# Nintendo_3DS_USB-C.net
KiCad netlist of a schematic drawn in EAGLE
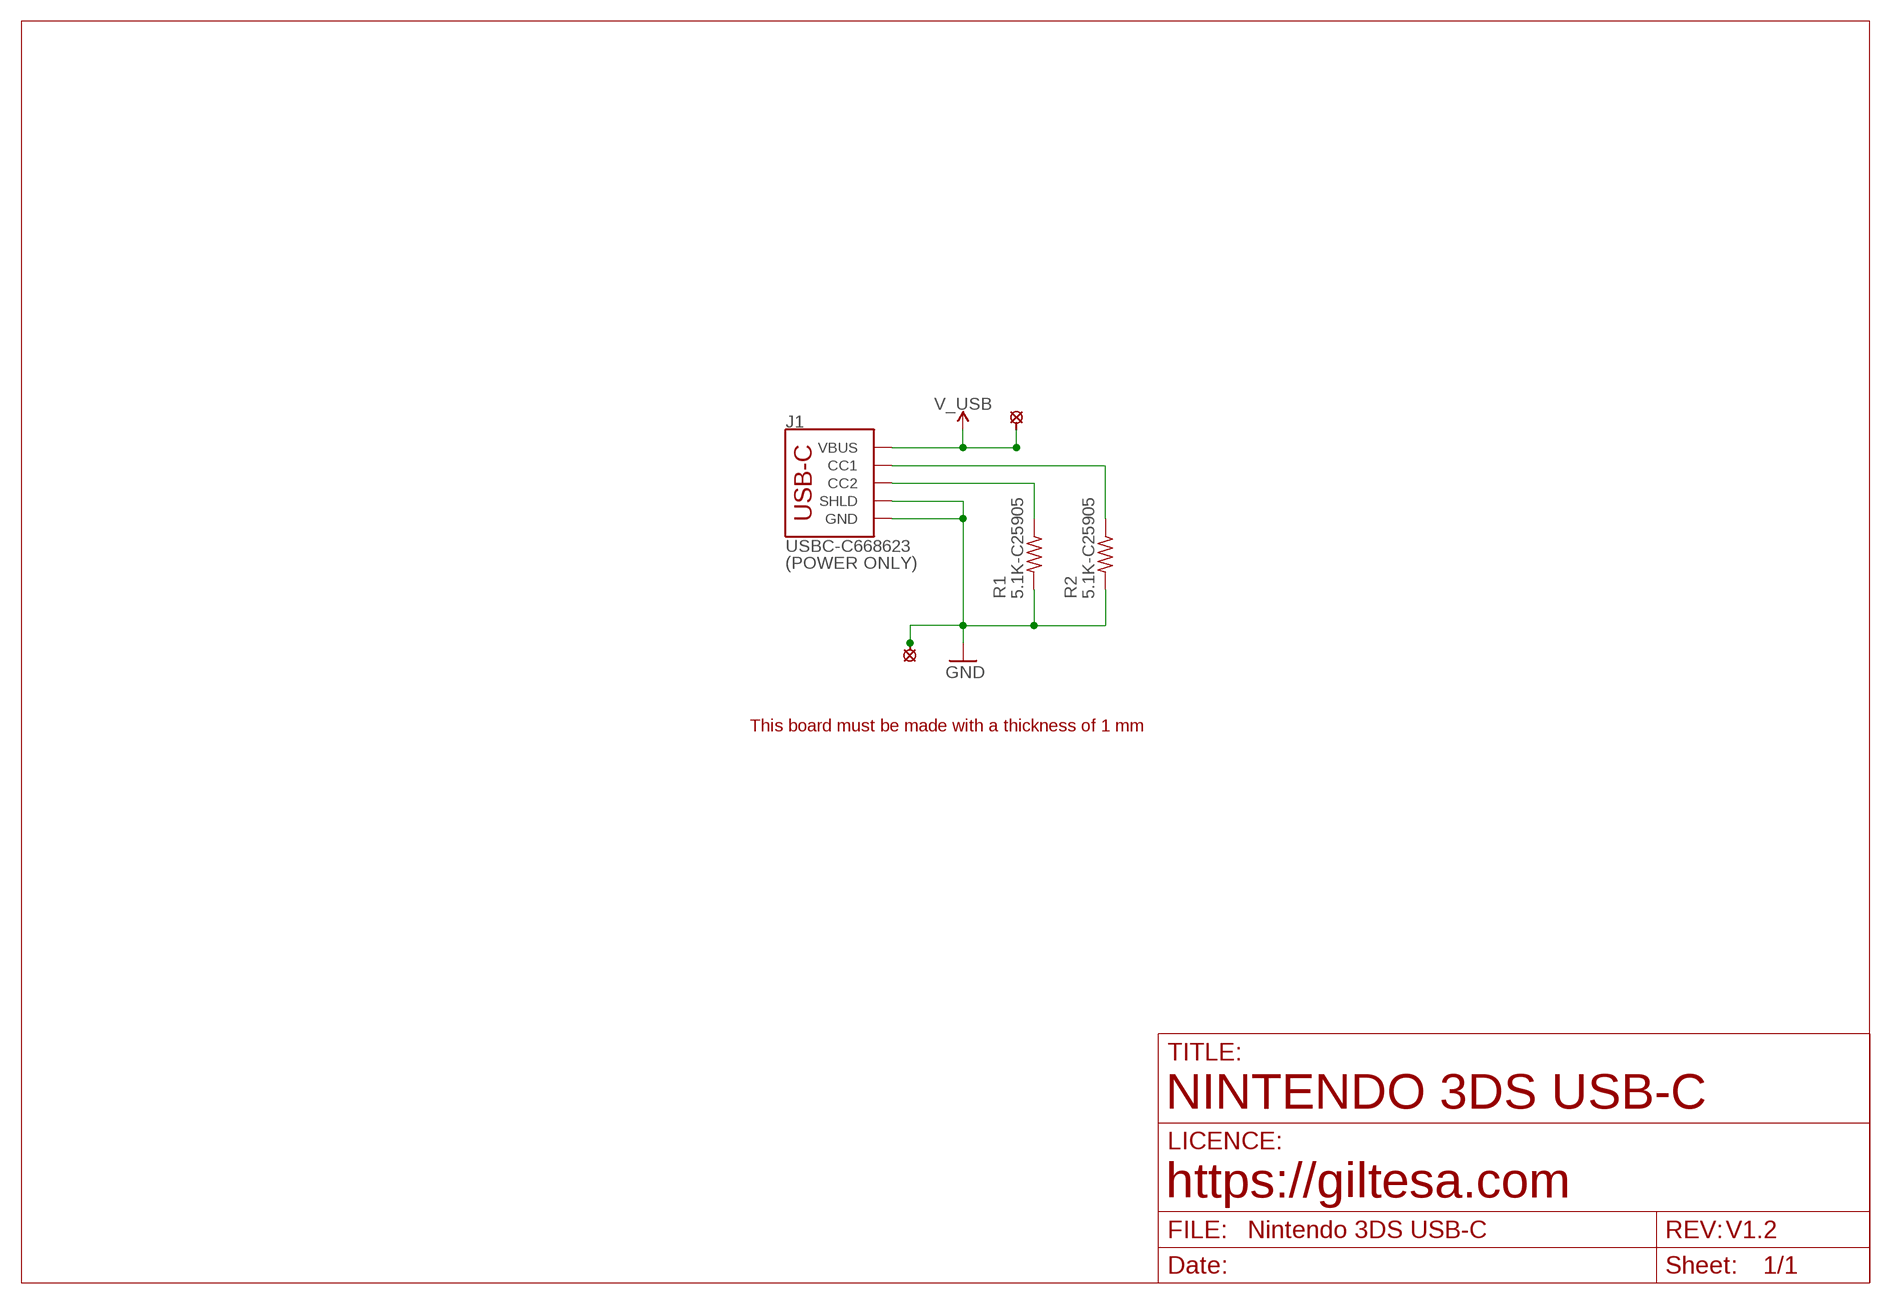
[diagram p0: schematic, sheet 1]

(export (version "E")
  (design (tool "Eeschema 10.0.6"))
  (components
    (comp (ref "J1")
      (value "USBC-C668623")
      (footprint "eagle-import:USB-C_6P")
      (libsource (lib "eagle-import") (part "USB-C_6P_POWER"))
    )
    (comp (ref "R1")
      (value "5.1K-C25905")
      (footprint "eagle-import:R0402")
      (libsource (lib "eagle-import") (part "R0402"))
    )
    (comp (ref "R2")
      (value "5.1K-C25905")
      (footprint "eagle-import:R0402")
      (libsource (lib "eagle-import") (part "R0402"))
    )
    (comp (ref "U$2")
      (value "PAD_1.0H")
      (footprint "eagle-import:PAD_1.0_HALF_MASK")
      (libsource (lib "eagle-import") (part "PAD_1.0H"))
    )
    (comp (ref "U$3")
      (value "PAD_1.0H")
      (footprint "eagle-import:PAD_1.0_HALF_MASK")
      (libsource (lib "eagle-import") (part "PAD_1.0H"))
    )
    (comp (ref "U$4")
      (value "PAD_1.0H")
      (footprint "eagle-import:PAD_1.0_HALF_MASK")
      (libsource (lib "eagle-import") (part "PAD_1.0H"))
    )
    (comp (ref "U$6")
      (value "PAD_1.0H")
      (footprint "eagle-import:PAD_1.0_HALF_MASK")
      (libsource (lib "eagle-import") (part "PAD_1.0H"))
    )
    (comp (ref "U$7")
      (value "PAD_1.0H")
      (footprint "eagle-import:PAD_1.0_HALF_MASK")
      (libsource (lib "eagle-import") (part "PAD_1.0H"))
    )
    (comp (ref "U$8")
      (value "PAD_1.0H")
      (footprint "eagle-import:PAD_1.0_HALF_MASK")
      (libsource (lib "eagle-import") (part "PAD_1.0H"))
    )
  )
  (nets
    (net (code "1") (name "GND") (class "Default")
      (node (ref "J1") (pin "A12-GND") (pinfunction "GND_A12-GND") (pintype "bidirectional"))
      (node (ref "J1") (pin "B12-GND") (pinfunction "GND_B12-GND") (pintype "bidirectional"))
      (node (ref "J1") (pin "SHLD1") (pinfunction "SHLD_SHLD1") (pintype "bidirectional"))
      (node (ref "J1") (pin "SHLD2") (pinfunction "SHLD_SHLD2") (pintype "bidirectional"))
      (node (ref "J1") (pin "SHLD3") (pinfunction "SHLD_SHLD3") (pintype "bidirectional"))
      (node (ref "J1") (pin "SHLD4") (pinfunction "SHLD_SHLD4") (pintype "bidirectional"))
      (node (ref "R1") (pin "2") (pinfunction "2_2") (pintype "passive"))
      (node (ref "R2") (pin "2") (pinfunction "2_2") (pintype "passive"))
      (node (ref "U$4") (pin "P$1") (pinfunction "P$1_P$1") (pintype "bidirectional"))
      (node (ref "U$6") (pin "P$1") (pinfunction "P$1_P$1") (pintype "bidirectional"))
      (node (ref "U$7") (pin "P$1") (pinfunction "P$1_P$1") (pintype "bidirectional"))
      (node (ref "U$8") (pin "P$1") (pinfunction "P$1_P$1") (pintype "bidirectional"))
    )
    (net (code "2") (name "Net-(J1-CC1)") (class "Default")
      (node (ref "J1") (pin "A5") (pinfunction "CC1_A5") (pintype "bidirectional"))
      (node (ref "R2") (pin "1") (pinfunction "1_1") (pintype "passive"))
    )
    (net (code "3") (name "Net-(J1-CC2)") (class "Default")
      (node (ref "J1") (pin "B5") (pinfunction "CC2_B5") (pintype "bidirectional"))
      (node (ref "R1") (pin "1") (pinfunction "1_1") (pintype "passive"))
    )
    (net (code "4") (name "V_USB") (class "Default")
      (node (ref "J1") (pin "A9-VBUS") (pinfunction "VBUS_A9-VBUS") (pintype "bidirectional"))
      (node (ref "J1") (pin "B9-VBUS") (pinfunction "VBUS_B9-VBUS") (pintype "bidirectional"))
      (node (ref "U$2") (pin "P$1") (pinfunction "P$1_P$1") (pintype "bidirectional"))
      (node (ref "U$3") (pin "P$1") (pinfunction "P$1_P$1") (pintype "bidirectional"))
    )
  )
)
